# DevBoard.net
KiCad netlist of a schematic drawn in Altium Designer
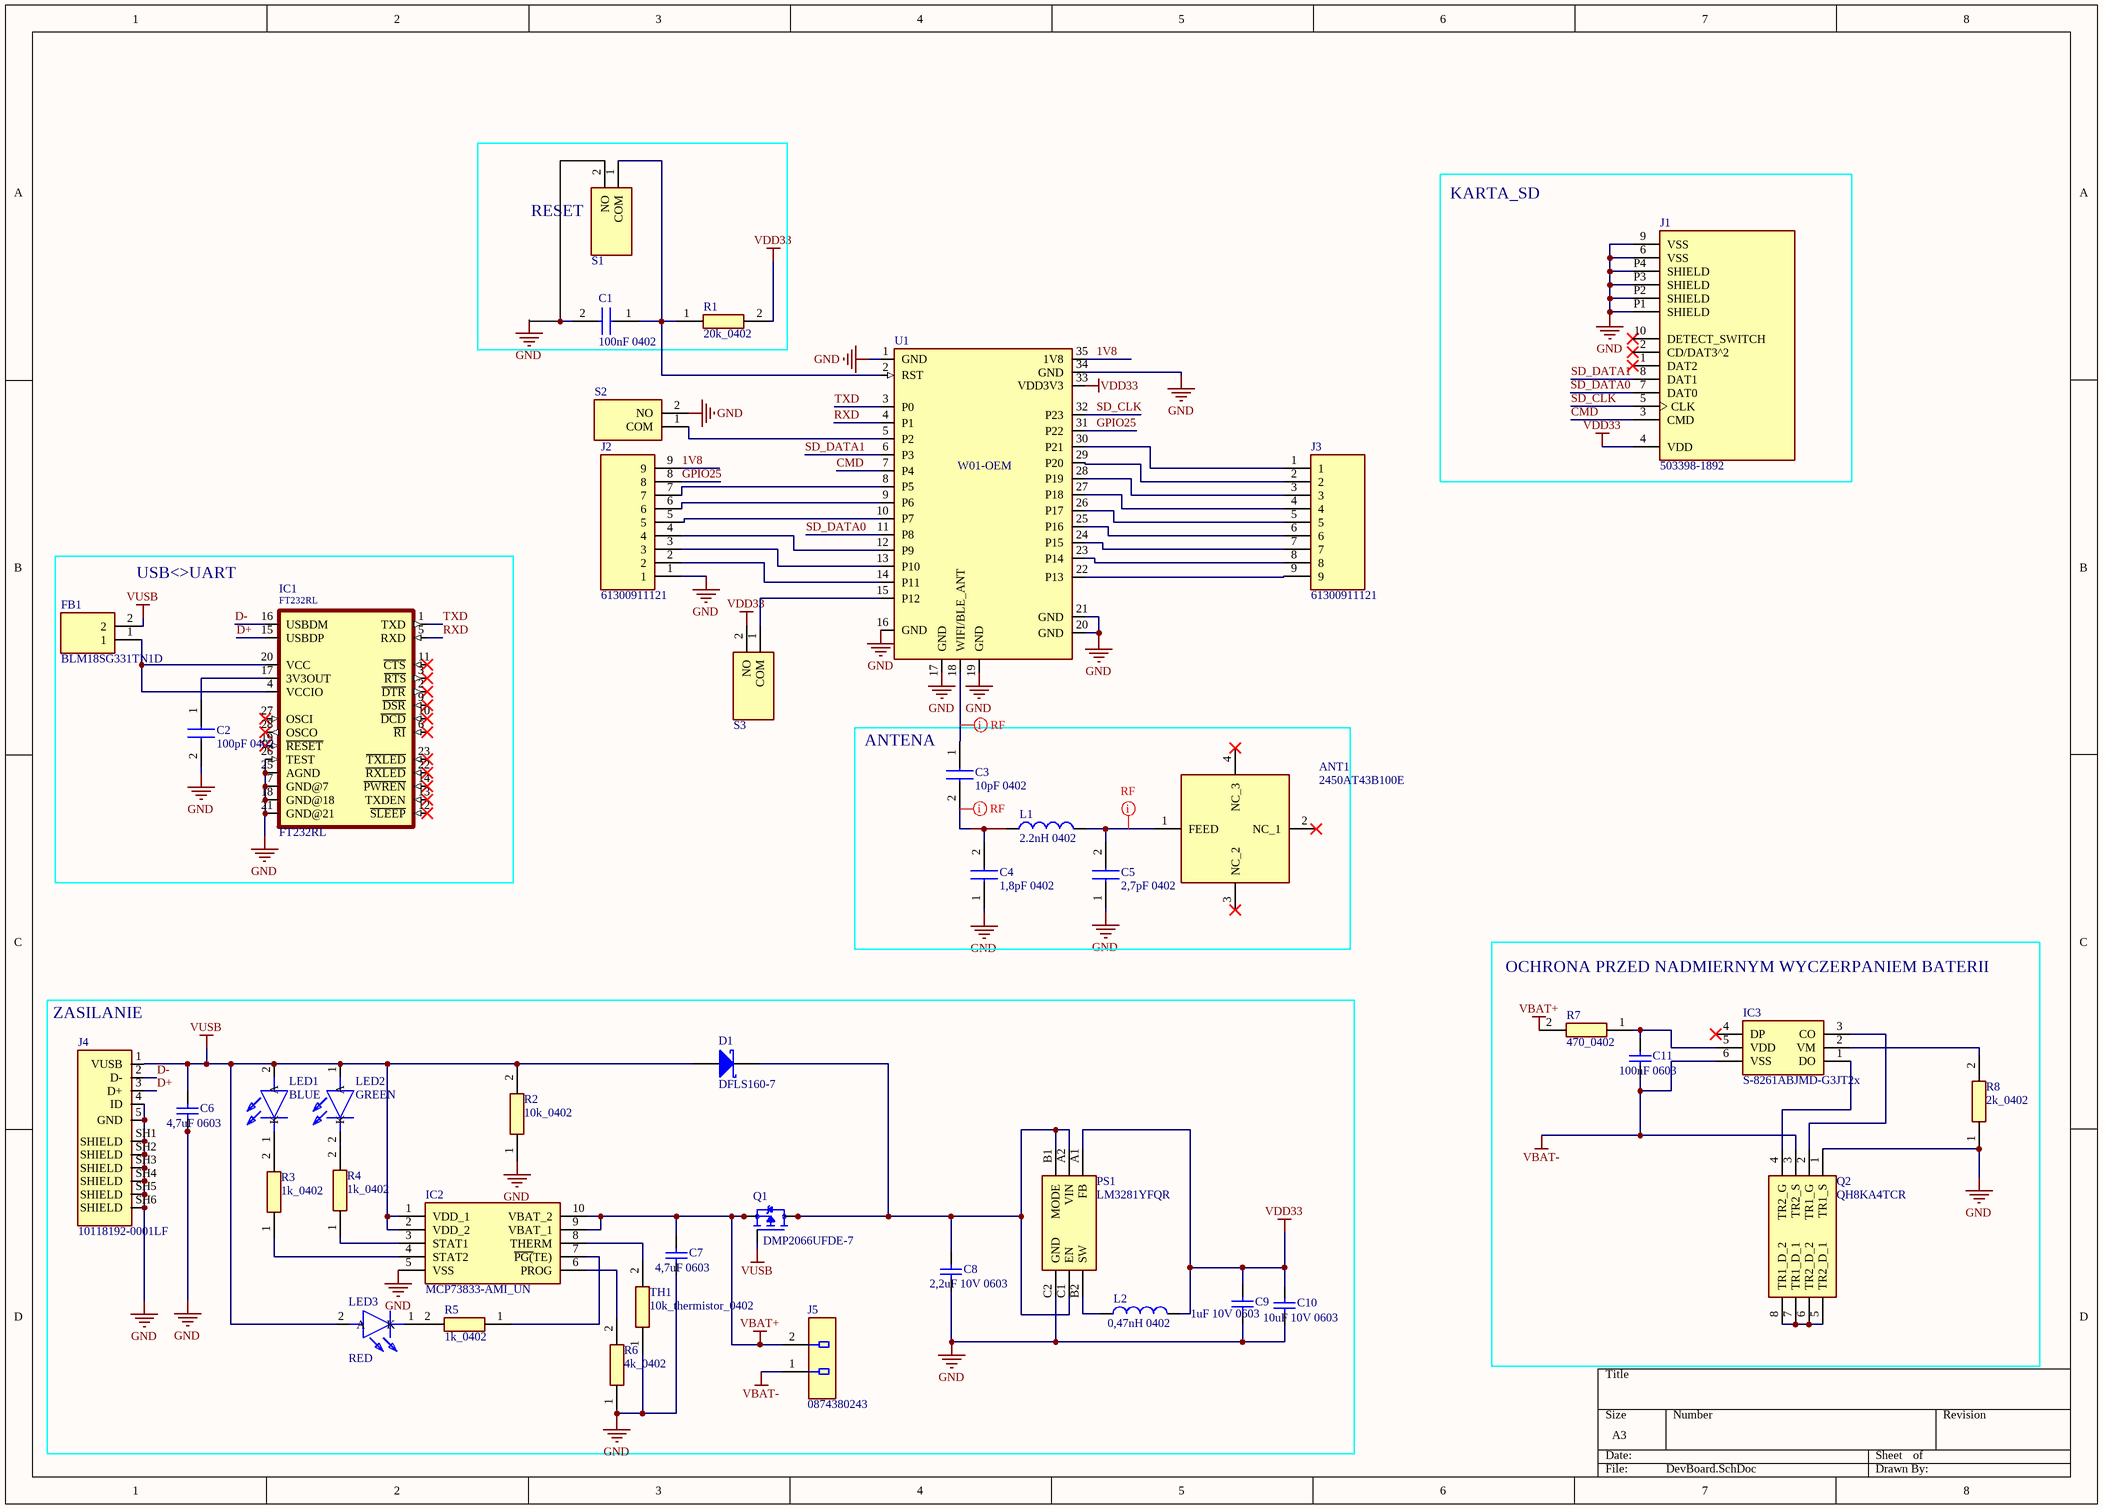
[diagram p0: DevBoard.SchDoc]

(export (version "E")
  (design (tool "Eeschema 10.0.6"))
  (components
    (comp (ref "ANT1")
      (value "2450AT43B100E")
      (footprint "SamacSys:2450AT43B100E")
      (description "Antenna")
      (fields (field (name "MOUSER PART NUMBER") "609-2450AT43B100E"))
      (libsource (lib "*") (part "2450AT43B100E"))
    )
    (comp (ref "C1")
      (value "100nF 0402")
      (footprint "SamacSys:CAPC1005X56N")
      (description "Capacitor")
      (fields
        (field (name "MANUFACTURER_PART_NUMBER") "04025A1R8BAT2A")
        (field (name "MOUSER PART NUMBER") "581-04025A1R8BAT2A")
      )
      (libsource (lib "*") (part "04025A1R8BAT2A"))
    )
    (comp (ref "C2")
      (value "100pF 0402")
      (footprint "SamacSys:CAPC1005X56N")
      (description "Capacitor")
      (fields
        (field (name "MANUFACTURER_PART_NUMBER") "04025A1R8BAT2A")
        (field (name "MOUSER PART NUMBER") "581-04025A1R8BAT2A")
      )
      (libsource (lib "*") (part "04025A1R8BAT2A"))
    )
    (comp (ref "C3")
      (value "10pF 0402")
      (footprint "SamacSys:CAPC1005X56N")
      (description "Capacitor")
      (fields
        (field (name "MANUFACTURER_PART_NUMBER") "04025A1R8BAT2A")
        (field (name "MOUSER PART NUMBER") "581-04025A1R8BAT2A")
      )
      (libsource (lib "*") (part "04025A1R8BAT2A"))
    )
    (comp (ref "C4")
      (value "1,8pF 0402")
      (footprint "SamacSys:CAPC1005X56N")
      (description "Capacitor")
      (fields
        (field (name "MANUFACTURER_PART_NUMBER") "04025A1R8BAT2A")
        (field (name "MOUSER PART NUMBER") "581-04025A1R8BAT2A")
      )
      (libsource (lib "*") (part "04025A1R8BAT2A"))
    )
    (comp (ref "C5")
      (value "2,7pF 0402")
      (footprint "SamacSys:CAPC1005X56N")
      (description "Capacitor")
      (fields
        (field (name "MANUFACTURER_PART_NUMBER") "04025A1R8BAT2A")
        (field (name "MOUSER PART NUMBER") "581-04025A1R8BAT2A")
      )
      (libsource (lib "*") (part "04025A1R8BAT2A"))
    )
    (comp (ref "C6")
      (value "4,7uF 0603")
      (footprint "CAPC0603(1608)100_L")
      (description "CAP 1uF 10V ±20% 0603 (1608 Metric) Thickness 1mm SMD")
      (fields (field (name "TOLERANCE") "Â±20%"))
      (libsource (lib "Altium Content Vault") (part "CMP-1035-02734-1"))
    )
    (comp (ref "C7")
      (value "4,7uF 0603")
      (footprint "CAPC0603(1608)100_L")
      (description "CAP 1uF 10V ±20% 0603 (1608 Metric) Thickness 1mm SMD")
      (fields (field (name "TOLERANCE") "Â±20%"))
      (libsource (lib "Altium Content Vault") (part "CMP-1035-02734-1"))
    )
    (comp (ref "C8")
      (value "2,2uF 10V 0603")
      (footprint "CAPC0603(1608)100_L")
      (description "CAP 1uF 10V ±20% 0603 (1608 Metric) Thickness 1mm SMD")
      (fields (field (name "TOLERANCE") "Â±20%"))
      (libsource (lib "Altium Content Vault") (part "CMP-1035-02734-1"))
    )
    (comp (ref "C9")
      (value "1uF 10V 0603")
      (footprint "CAPC0603(1608)100_L")
      (description "CAP 1uF 10V ±20% 0603 (1608 Metric) Thickness 1mm SMD")
      (fields (field (name "TOLERANCE") "Â±20%"))
      (libsource (lib "Altium Content Vault") (part "CAP"))
    )
    (comp (ref "C10")
      (value "10uF 10V 0603")
      (footprint "CAPC0603(1608)100_L")
      (description "CAP 1uF 10V ±20% 0603 (1608 Metric) Thickness 1mm SMD")
      (fields (field (name "TOLERANCE") "Â±20%"))
      (libsource (lib "Altium Content Vault") (part "CMP-1035-02734-1"))
    )
    (comp (ref "C11")
      (value "100nF 0603")
      (footprint "CAPC0603(1608)100_L")
      (description "CAP 1uF 10V ±20% 0603 (1608 Metric) Thickness 1mm SMD")
      (fields (field (name "TOLERANCE") "Â±20%"))
      (libsource (lib "Altium Content Vault") (part "CMP-1035-02734-1"))
    )
    (comp (ref "D1")
      (value "DFLS160-7")
      (footprint "DIOD-POWERDI123-2_V")
      (description "Schottky Barrier Rectifier, 60 V, 1 A, -65 to 150 degC, 2-Pin SMD, RoHS, Tape and Reel")
      (fields (field (name "MANUFACTURER") "Diodes Inc"))
      (libsource (lib "Altium Content Vault") (part "CMP-2000-07449-1"))
    )
    (comp (ref "FB1")
      (value "BLM18SG331TN1D")
      (footprint "SamacSys:BLM18SG121TN1J")
      (description "Ferrite Bead")
      (fields (field (name "MOUSER PART NUMBER") "81-BLM18SG331TN1D"))
      (libsource (lib "*") (part "BLM18SG331TN1D"))
    )
    (comp (ref "IC1")
      (value "FT232RL")
      (footprint "SSOP28-LD")
      (description "USB ë¸Œë¦¬ì§€, USB-UART USB 2.0 UART ì¸í„°íŽ˜ì´ìŠ¤ 28-SSOP")
      (fields (field (name "MF") "FTDI, Future"))
      (libsource (lib "FT232RL") (part "FT232RL"))
    )
    (comp (ref "IC2")
      (value "MCP73833-AMI_UN")
      (footprint "SamacSys:SOP50P490X110-10N")
      (description "Integrated Circuit")
      (fields
        (field (name "MANUFACTURER_PART_NUMBER") "MCP73833-AMI/UN")
        (field (name "MOUSER PART NUMBER") "579-MCP73833-AMI/UN")
      )
      (libsource (lib "*") (part "MCP73833-AMI_UN"))
    )
    (comp (ref "IC3")
      (value "S-8261ABJMD-G3JT2x")
      (footprint "SamacSys:SOT95P275X135-6N")
      (description "Integrated Circuit")
      (fields (field (name "MOUSER PART NUMBER") "628-S8261ACMMDG4MT2G"))
      (libsource (lib "*") (part "S-8261ACMMD-G4MT2U"))
    )
    (comp (ref "J1")
      (value "503398-1892")
      (footprint "MOLEX_503398-1892")
      (description "9 _8 + 1_ Position Card Connector microSDâ„¢ Surface Mount, Right Angle Gold")
      (fields (field (name "MP") "5033981892") (field (name "DIGI-KEY_PART_NUMBER") "WM11190CT-ND"))
      (libsource (lib "503398-1892") (part "503398-1892"))
    )
    (comp (ref "J2")
      (value "61300911121")
      (footprint "SamacSys:HDRV9W95P0X254_1X9_2286X254X874P")
      (description "Connector")
      (fields (field (name "MOUSER PART NUMBER") "710-61300911121"))
      (libsource (lib "*") (part "61300911121"))
    )
    (comp (ref "J3")
      (value "61300911121")
      (footprint "SamacSys:HDRV9W95P0X254_1X9_2286X254X874P")
      (description "Connector")
      (fields (field (name "MOUSER PART NUMBER") "710-61300911121"))
      (libsource (lib "") (part "61300911121_1"))
    )
    (comp (ref "J4")
      (value "10118192-0001LF")
      (footprint "SamacSys:101181920001LF")
      (description "USB - micro B USB 2.0 Receptacle Connector 5 Position Surface Mount, Right Angle")
      (fields (field (name "MF") "Amphenol ICC"))
      (libsource (lib "10118192-0001LF") (part "10118192-0001LF"))
    )
    (comp (ref "J5")
      (value "Conn_Molex_0874380243_eec")
      (footprint "Molex_0874380243_0")
      (description "CONN HEADER 2POS 1.5MM R/A SMD")
      (fields
        (field (name "PART NUMBER") "0874380243")
        (field (name "MANUFACTURER") "Molex")
        (field (name "MOUSER PART NUMBER") "538-87438-0243")
      )
      (libsource (lib "Conn_Molex_0874380243_eec") (part "Conn_Molex_0874380243_eec"))
    )
    (comp (ref "L1")
      (value "2.2nH 0402")
      (footprint "INDC1006X60X20LL10T10")
      (description "Chip Inductor, 10 nH, +/- 5%, 500 mA, -55 to 125 degC, 0402 (1005 Metric), RoHS, Tape and Reel")
      (fields (field (name "MANUFACTURER") "Murata"))
      (libsource (lib "Altium Content Vault") (part "IND-2"))
    )
    (comp (ref "L2")
      (value "0,47nH 0402")
      (footprint "INDC1006X60X20LL10T10")
      (description "Chip Inductor, 10 nH, +/- 5%, 500 mA, -55 to 125 degC, 0402 (1005 Metric), RoHS, Tape and Reel")
      (fields (field (name "MANUFACTURER") "Murata"))
      (libsource (lib "Altium Content Vault") (part "IND-2"))
    )
    (comp (ref "LED1")
      (value "BLUE")
      (footprint "SamacSys:KBDELPS212QHRI24Z55510S")
      (description "LED_BLUE")
      (fields
        (field (name "MANUFACTURER_PART_NUMBER") "KB DELPS2.12-QHRI-24-Z555-10-S")
        (field (name "MOUSER PART NUMBER") "720-KBDELPS212A6350")
      )
      (libsource (lib "*") (part "KB_DELPS2.12-QHRI-24-Z555-10-S"))
    )
    (comp (ref "LED2")
      (value "GREEN")
      (footprint "SamacSys:KGDELLS122JGKH24")
      (description "LED_GREEN")
      (fields
        (field (name "MANUFACTURER_PART_NUMBER") "KG DELLS1.22-JGKH-24")
        (field (name "MOUSER PART NUMBER") "720-KGDELLS122A4849")
      )
      (libsource (lib "*") (part "KG_DELLS1.22-JGKH-24"))
    )
    (comp (ref "LED3")
      (value "RED")
      (footprint "SamacSys:KRDELPS122UHVI26H3Q4")
      (description "LED_RED")
      (fields
        (field (name "MANUFACTURER_PART_NUMBER") "KR DELPS1.22-UHVI-26-H3Q4")
        (field (name "MOUSER PART NUMBER") "720-KRDELPS122A5163")
      )
      (libsource (lib "*") (part "KR_DELPS1.22-UHVI-26-H3Q4"))
    )
    (comp (ref "PS1")
      (value "LM3281YFQR")
      (footprint "SamacSys:BGA6C40P2X3_116X144X68")
      (description "Power Supply")
      (fields (field (name "MOUSER PART NUMBER") "595-LM3281YFQR"))
      (libsource (lib "*") (part "LM3281YFQR"))
    )
    (comp (ref "Q1")
      (value "DMP2066UFDE-7")
      (footprint "MOSFET_DMP2066UFDE-7")
      (description "P-Channel 20V 6.2A (Ta) 660mW (Ta) Surface Mount U-DFN2020-6 (Type E)")
      (fields (field (name "MF") "Diodes Inc."))
      (libsource (lib "DMP2066UFDE-7") (part "DMP2066UFDE-7"))
    )
    (comp (ref "Q2")
      (value "QH8KA4TCR")
      (footprint "SamacSys:SOTFL65P280X85-8N")
      (description "MOSFET (N-Channel)")
      (fields (field (name "MOUSER PART NUMBER") "755-QH8KA4TCR"))
      (libsource (lib "*") (part "QH8KA4TCR"))
    )
    (comp (ref "R1")
      (value "20k_0402")
      (footprint "SamacSys:RESC1005X40N")
      (description "Resistor")
      (fields
        (field (name "MANUFACTURER_PART_NUMBER") "CR0402-FX-2002GLF")
        (field (name "MOUSER PART NUMBER") "652-CR0402FX-2002GLF")
      )
      (libsource (lib "") (part "CR0402-FX-2002GLF_2"))
    )
    (comp (ref "R2")
      (value "10k_0402")
      (footprint "SamacSys:RESC1005X40N")
      (description "Resistor")
      (fields
        (field (name "MANUFACTURER_PART_NUMBER") "CR0402-FX-2002GLF")
        (field (name "MOUSER PART NUMBER") "652-CR0402FX-2002GLF")
      )
      (libsource (lib "") (part "CR0402-FX-2002GLF_1"))
    )
    (comp (ref "R3")
      (value "1k_0402")
      (footprint "SamacSys:RESC1005X40N")
      (description "Resistor")
      (fields
        (field (name "MANUFACTURER_PART_NUMBER") "CR0402-FX-2002GLF")
        (field (name "MOUSER PART NUMBER") "652-CR0402FX-2002GLF")
      )
      (libsource (lib "") (part "CR0402-FX-2002GLF_1"))
    )
    (comp (ref "R4")
      (value "1k_0402")
      (footprint "SamacSys:RESC1005X40N")
      (description "Resistor")
      (fields
        (field (name "MANUFACTURER_PART_NUMBER") "CR0402-FX-2002GLF")
        (field (name "MOUSER PART NUMBER") "652-CR0402FX-2002GLF")
      )
      (libsource (lib "") (part "CR0402-FX-2002GLF_1"))
    )
    (comp (ref "R5")
      (value "1k_0402")
      (footprint "SamacSys:RESC1005X40N")
      (description "Resistor")
      (fields
        (field (name "MANUFACTURER_PART_NUMBER") "CR0402-FX-2002GLF")
        (field (name "MOUSER PART NUMBER") "652-CR0402FX-2002GLF")
      )
      (libsource (lib "*") (part "CR0402-FX-2002GLF"))
    )
    (comp (ref "R6")
      (value "4k_0402")
      (footprint "SamacSys:RESC1005X40N")
      (description "Resistor")
      (fields
        (field (name "MANUFACTURER_PART_NUMBER") "CR0402-FX-2002GLF")
        (field (name "MOUSER PART NUMBER") "652-CR0402FX-2002GLF")
      )
      (libsource (lib "") (part "CR0402-FX-2002GLF_1"))
    )
    (comp (ref "R7")
      (value "470_0402")
      (footprint "SamacSys:RESC1005X40N")
      (description "Resistor")
      (fields
        (field (name "MANUFACTURER_PART_NUMBER") "CR0402-FX-2002GLF")
        (field (name "MOUSER PART NUMBER") "652-CR0402FX-2002GLF")
      )
      (libsource (lib "*") (part "CR0402-FX-2002GLF"))
    )
    (comp (ref "R8")
      (value "2k_0402")
      (footprint "SamacSys:RESC1005X40N")
      (description "Resistor")
      (fields
        (field (name "MANUFACTURER_PART_NUMBER") "CR0402-FX-2002GLF")
        (field (name "MOUSER PART NUMBER") "652-CR0402FX-2002GLF")
      )
      (libsource (lib "") (part "CR0402-FX-2002GLF_1"))
    )
    (comp (ref "S1")
      (value "PTS636_SM43J_SMTR_LFS")
      (footprint "SamacSys:PTS636SM43JSMTRLFS")
      (description "Switch")
      (fields
        (field (name "MANUFACTURER_PART_NUMBER") "PTS636 SM43J SMTR LFS")
        (field (name "MOUSER PART NUMBER") "611-PTS636SM43JSMTRL")
      )
      (libsource (lib "*") (part "PTS636_SM43J_SMTR_LFS"))
    )
    (comp (ref "S2")
      (value "PTS636_SM43J_SMTR_LFS")
      (footprint "SamacSys:PTS636SM43JSMTRLFS")
      (description "Switch")
      (fields
        (field (name "MANUFACTURER_PART_NUMBER") "PTS636 SM43J SMTR LFS")
        (field (name "MOUSER PART NUMBER") "611-PTS636SM43JSMTRL")
      )
      (libsource (lib "") (part "PTS636_SM43J_SMTR_LFS_1"))
    )
    (comp (ref "S3")
      (value "PTS636_SM43J_SMTR_LFS")
      (footprint "SamacSys:PTS636SM43JSMTRLFS")
      (description "Switch")
      (fields
        (field (name "MANUFACTURER_PART_NUMBER") "PTS636 SM43J SMTR LFS")
        (field (name "MOUSER PART NUMBER") "611-PTS636SM43JSMTRL")
      )
      (libsource (lib "*") (part "PTS636_SM43J_SMTR_LFS"))
    )
    (comp (ref "TH1")
      (value "10k_thermistor_0402")
      (footprint "SamacSys:RESC1005X40N")
      (description "NCU15XH103D60RC")
      (fields
        (field (name "MANUFACTURER_PART_NUMBER") "CR0402-FX-2002GLF")
        (field (name "MOUSER PART NUMBER") "652-CR0402FX-2002GLF")
      )
      (libsource (lib "") (part "CR0402-FX-2002GLF_1"))
    )
    (comp (ref "U1")
      (value "W01-OEM")
      (footprint "SnapEDApcb:PYCOM_W01-OEM")
      (fields (field (name "MF") "Pycom"))
      (libsource (lib "SnapEDAsch") (part "W01-OEM"))
    )
  )
  (nets
    (net (code "1") (name "/1V8") (class "Default")
      (node (ref "J2") (pin "9") (pinfunction "9_9") (pintype "passive"))
      (node (ref "U1") (pin "35") (pinfunction "1V8_35") (pintype "power_in"))
    )
    (net (code "2") (name "/CMD") (class "Default")
      (node (ref "J1") (pin "3") (pinfunction "CMD_3") (pintype "passive"))
      (node (ref "U1") (pin "7") (pinfunction "P4_7") (pintype "bidirectional"))
    )
    (net (code "3") (name "/D+") (class "Default")
      (node (ref "IC1") (pin "15") (pinfunction "USBDP_15") (pintype "bidirectional"))
      (node (ref "J4") (pin "3") (pinfunction "D+_3") (pintype "passive"))
    )
    (net (code "4") (name "/D-") (class "Default")
      (node (ref "IC1") (pin "16") (pinfunction "USBDM_16") (pintype "bidirectional"))
      (node (ref "J4") (pin "2") (pinfunction "D-_2") (pintype "passive"))
    )
    (net (code "5") (name "/GPIO25") (class "Default")
      (node (ref "J2") (pin "8") (pinfunction "8_8") (pintype "passive"))
      (node (ref "U1") (pin "31") (pinfunction "P22_31") (pintype "bidirectional"))
    )
    (net (code "6") (name "/RXD") (class "Default")
      (node (ref "IC1") (pin "5") (pinfunction "RXD_5") (pintype "input"))
      (node (ref "U1") (pin "4") (pinfunction "P1_4") (pintype "bidirectional"))
    )
    (net (code "7") (name "/SD_CLK") (class "Default")
      (node (ref "J1") (pin "5") (pinfunction "CLK_5") (pintype "passive"))
      (node (ref "U1") (pin "32") (pinfunction "P23_32") (pintype "bidirectional"))
    )
    (net (code "8") (name "/SD_DATA0") (class "Default")
      (node (ref "J1") (pin "7") (pinfunction "DAT0_7") (pintype "passive"))
      (node (ref "U1") (pin "11") (pinfunction "P8_11") (pintype "bidirectional"))
    )
    (net (code "9") (name "/SD_DATA1") (class "Default")
      (node (ref "J1") (pin "8") (pinfunction "DAT1_8") (pintype "passive"))
      (node (ref "U1") (pin "6") (pinfunction "P3_6") (pintype "bidirectional"))
    )
    (net (code "10") (name "/TXD") (class "Default")
      (node (ref "IC1") (pin "1") (pinfunction "TXD_1") (pintype "output"))
      (node (ref "U1") (pin "3") (pinfunction "P0_3") (pintype "bidirectional"))
    )
    (net (code "11") (name "GND") (class "Default")
      (node (ref "C1") (pin "2") (pinfunction "2_2") (pintype "passive"))
      (node (ref "C10") (pin "1") (pinfunction "1_1") (pintype "passive"))
      (node (ref "C2") (pin "2") (pinfunction "2_2") (pintype "passive"))
      (node (ref "C4") (pin "1") (pinfunction "1_1") (pintype "passive"))
      (node (ref "C5") (pin "1") (pinfunction "1_1") (pintype "passive"))
      (node (ref "C6") (pin "1") (pinfunction "1_1") (pintype "passive"))
      (node (ref "C7") (pin "1") (pinfunction "1_1") (pintype "passive"))
      (node (ref "C8") (pin "1") (pinfunction "1_1") (pintype "passive"))
      (node (ref "C9") (pin "1") (pinfunction "1_1") (pintype "passive"))
      (node (ref "IC1") (pin "18") (pinfunction "GND@18_18") (pintype "power_in"))
      (node (ref "IC1") (pin "21") (pinfunction "GND@21_21") (pintype "power_in"))
      (node (ref "IC1") (pin "25") (pinfunction "AGND_25") (pintype "power_in"))
      (node (ref "IC1") (pin "26") (pinfunction "TEST_26") (pintype "input"))
      (node (ref "IC1") (pin "7") (pinfunction "GND@7_7") (pintype "power_in"))
      (node (ref "IC2") (pin "5") (pinfunction "VSS_5") (pintype "passive"))
      (node (ref "J1") (pin "6") (pinfunction "VSS_6") (pintype "power_in"))
      (node (ref "J1") (pin "9") (pinfunction "VSS_9") (pintype "power_in"))
      (node (ref "J1") (pin "P1") (pinfunction "SHIELD_P1") (pintype "passive"))
      (node (ref "J1") (pin "P2") (pinfunction "SHIELD_P2") (pintype "passive"))
      (node (ref "J1") (pin "P3") (pinfunction "SHIELD_P3") (pintype "passive"))
      (node (ref "J1") (pin "P4") (pinfunction "SHIELD_P4") (pintype "passive"))
      (node (ref "J2") (pin "1") (pinfunction "1_1") (pintype "passive"))
      (node (ref "J4") (pin "4") (pinfunction "ID_4") (pintype "passive"))
      (node (ref "J4") (pin "5") (pinfunction "GND_5") (pintype "passive"))
      (node (ref "J4") (pin "SH1") (pinfunction "SHIELD_SH1") (pintype "passive"))
      (node (ref "J4") (pin "SH2") (pinfunction "SHIELD_SH2") (pintype "passive"))
      (node (ref "J4") (pin "SH3") (pinfunction "SHIELD_SH3") (pintype "passive"))
      (node (ref "J4") (pin "SH4") (pinfunction "SHIELD_SH4") (pintype "passive"))
      (node (ref "J4") (pin "SH5") (pinfunction "SHIELD_SH5") (pintype "passive"))
      (node (ref "J4") (pin "SH6") (pinfunction "SHIELD_SH6") (pintype "passive"))
      (node (ref "PS1") (pin "C2") (pinfunction "GND_C2") (pintype "passive"))
      (node (ref "Q2") (pin "1") (pinfunction "TR1_S_1") (pintype "passive"))
      (node (ref "R2") (pin "1") (pinfunction "1_1") (pintype "passive"))
      (node (ref "R6") (pin "1") (pinfunction "1_1") (pintype "passive"))
      (node (ref "R8") (pin "1") (pinfunction "1_1") (pintype "passive"))
      (node (ref "S1") (pin "2") (pinfunction "NO_2") (pintype "passive"))
      (node (ref "S2") (pin "2") (pinfunction "NO_2") (pintype "passive"))
      (node (ref "TH1") (pin "1") (pinfunction "1_1") (pintype "passive"))
      (node (ref "U1") (pin "1") (pinfunction "GND_1") (pintype "power_in"))
      (node (ref "U1") (pin "16") (pinfunction "GND_16") (pintype "power_in"))
      (node (ref "U1") (pin "17") (pinfunction "GND_17") (pintype "power_in"))
      (node (ref "U1") (pin "19") (pinfunction "GND_19") (pintype "power_in"))
      (node (ref "U1") (pin "20") (pinfunction "GND_20") (pintype "power_in"))
      (node (ref "U1") (pin "21") (pinfunction "GND_21") (pintype "power_in"))
      (node (ref "U1") (pin "34") (pinfunction "GND_34") (pintype "power_in"))
    )
    (net (code "12") (name "Net-(ANT1-FEED)") (class "Default")
      (node (ref "ANT1") (pin "1") (pinfunction "FEED_1") (pintype "passive"))
      (node (ref "C5") (pin "2") (pinfunction "2_2") (pintype "passive"))
      (node (ref "L1") (pin "2") (pinfunction "2_2") (pintype "passive"))
    )
    (net (code "13") (name "Net-(C3-Pad2)") (class "Default")
      (node (ref "C3") (pin "2") (pinfunction "2_2") (pintype "passive"))
      (node (ref "C4") (pin "2") (pinfunction "2_2") (pintype "passive"))
      (node (ref "L1") (pin "1") (pinfunction "1_1") (pintype "passive"))
    )
    (net (code "14") (name "Net-(D1-K)") (class "Default")
      (node (ref "C8") (pin "2") (pinfunction "2_2") (pintype "passive"))
      (node (ref "D1") (pin "2") (pinfunction "K_2") (pintype "passive"))
      (node (ref "PS1") (pin "A2") (pinfunction "VIN_A2") (pintype "passive"))
      (node (ref "PS1") (pin "B1") (pinfunction "MODE_B1") (pintype "passive"))
      (node (ref "PS1") (pin "C1") (pinfunction "EN_C1") (pintype "passive"))
      (node (ref "Q1") (pin "1") (pinfunction "D_1") (pintype "passive"))
      (node (ref "Q1") (pin "2") (pinfunction "D_2") (pintype "passive"))
      (node (ref "Q1") (pin "5") (pinfunction "D_5") (pintype "passive"))
      (node (ref "Q1") (pin "6") (pinfunction "D_6") (pintype "passive"))
    )
    (net (code "15") (name "Net-(IC1-3V3OUT)") (class "Default")
      (node (ref "C2") (pin "1") (pinfunction "1_1") (pintype "passive"))
      (node (ref "IC1") (pin "17") (pinfunction "3V3OUT_17") (pintype "power_in"))
    )
    (net (code "16") (name "Net-(IC1-VCC)") (class "Default")
      (node (ref "FB1") (pin "1") (pinfunction "1_1") (pintype "passive"))
      (node (ref "IC1") (pin "20") (pinfunction "VCC_20") (pintype "power_in"))
      (node (ref "IC1") (pin "4") (pinfunction "VCCIO_4") (pintype "power_in"))
    )
    (net (code "17") (name "Net-(IC2-PROG)") (class "Default")
      (node (ref "IC2") (pin "6") (pinfunction "PROG_6") (pintype "passive"))
      (node (ref "R6") (pin "2") (pinfunction "2_2") (pintype "passive"))
    )
    (net (code "18") (name "Net-(IC2-STAT1)") (class "Default")
      (node (ref "IC2") (pin "3") (pinfunction "STAT1_3") (pintype "passive"))
      (node (ref "R4") (pin "1") (pinfunction "1_1") (pintype "passive"))
    )
    (net (code "19") (name "Net-(IC2-STAT2)") (class "Default")
      (node (ref "IC2") (pin "4") (pinfunction "STAT2_4") (pintype "passive"))
      (node (ref "R3") (pin "1") (pinfunction "1_1") (pintype "passive"))
    )
    (net (code "20") (name "Net-(IC2-THERM)") (class "Default")
      (node (ref "IC2") (pin "8") (pinfunction "THERM_8") (pintype "passive"))
      (node (ref "TH1") (pin "2") (pinfunction "2_2") (pintype "passive"))
    )
    (net (code "21") (name "Net-(IC2-~{PG(}TE))") (class "Default")
      (node (ref "IC2") (pin "7") (pinfunction "~{PG(}TE)_7") (pintype "passive"))
      (node (ref "R5") (pin "1") (pinfunction "1_1") (pintype "passive"))
    )
    (net (code "22") (name "Net-(IC3-CO)") (class "Default")
      (node (ref "IC3") (pin "3") (pinfunction "CO_3") (pintype "passive"))
      (node (ref "Q2") (pin "2") (pinfunction "TR1_G_2") (pintype "passive"))
    )
    (net (code "23") (name "Net-(IC3-DO)") (class "Default")
      (node (ref "IC3") (pin "1") (pinfunction "DO_1") (pintype "passive"))
      (node (ref "Q2") (pin "4") (pinfunction "TR2_G_4") (pintype "passive"))
    )
    (net (code "24") (name "Net-(IC3-VDD)") (class "Default")
      (node (ref "C11") (pin "2") (pinfunction "2_2") (pintype "passive"))
      (node (ref "IC3") (pin "5") (pinfunction "VDD_5") (pintype "passive"))
      (node (ref "R7") (pin "1") (pinfunction "1_1") (pintype "passive"))
    )
    (net (code "25") (name "Net-(IC3-VM)") (class "Default")
      (node (ref "IC3") (pin "2") (pinfunction "VM_2") (pintype "passive"))
      (node (ref "R8") (pin "2") (pinfunction "2_2") (pintype "passive"))
    )
    (net (code "26") (name "Net-(LED1-K)") (class "Default")
      (node (ref "LED1") (pin "1") (pinfunction "K_1") (pintype "passive"))
      (node (ref "R3") (pin "2") (pinfunction "2_2") (pintype "passive"))
    )
    (net (code "27") (name "Net-(LED2-K)") (class "Default")
      (node (ref "LED2") (pin "2") (pinfunction "K_2") (pintype "passive"))
      (node (ref "R4") (pin "2") (pinfunction "2_2") (pintype "passive"))
    )
    (net (code "28") (name "Net-(LED3-K)") (class "Default")
      (node (ref "LED3") (pin "1") (pinfunction "K_1") (pintype "passive"))
      (node (ref "R5") (pin "2") (pinfunction "2_2") (pintype "passive"))
    )
    (net (code "29") (name "Net-(PS1-SW)") (class "Default")
      (node (ref "L2") (pin "1") (pinfunction "1_1") (pintype "passive"))
      (node (ref "PS1") (pin "B2") (pinfunction "SW_B2") (pintype "passive"))
    )
    (net (code "30") (name "Net-(Q2-TR1_D_1)") (class "Default")
      (node (ref "Q2") (pin "5") (pinfunction "TR2_D_1_5") (pintype "passive"))
      (node (ref "Q2") (pin "6") (pinfunction "TR2_D_2_6") (pintype "passive"))
      (node (ref "Q2") (pin "7") (pinfunction "TR1_D_1_7") (pintype "passive"))
      (node (ref "Q2") (pin "8") (pinfunction "TR1_D_2_8") (pintype "passive"))
    )
    (net (code "31") (name "Net-(S1-COM)") (class "Default")
      (node (ref "C1") (pin "1") (pinfunction "1_1") (pintype "passive"))
      (node (ref "R1") (pin "1") (pinfunction "1_1") (pintype "passive"))
      (node (ref "S1") (pin "1") (pinfunction "COM_1") (pintype "passive"))
      (node (ref "U1") (pin "2") (pinfunction "RST_2") (pintype "input"))
    )
    (net (code "32") (name "Net-(S2-COM)") (class "Default")
      (node (ref "S2") (pin "1") (pinfunction "COM_1") (pintype "passive"))
      (node (ref "U1") (pin "5") (pinfunction "P2_5") (pintype "bidirectional"))
    )
    (net (code "33") (name "Net-(S3-COM)") (class "Default")
      (node (ref "S3") (pin "1") (pinfunction "COM_1") (pintype "passive"))
      (node (ref "U1") (pin "15") (pinfunction "P12_15") (pintype "bidirectional"))
    )
    (net (code "34") (name "Net-(U1-P5)") (class "Default")
      (node (ref "J2") (pin "7") (pinfunction "7_7") (pintype "passive"))
      (node (ref "U1") (pin "8") (pinfunction "P5_8") (pintype "bidirectional"))
    )
    (net (code "35") (name "Net-(U1-P6)") (class "Default")
      (node (ref "J2") (pin "6") (pinfunction "6_6") (pintype "passive"))
      (node (ref "U1") (pin "9") (pinfunction "P6_9") (pintype "bidirectional"))
    )
    (net (code "36") (name "Net-(U1-P7)") (class "Default")
      (node (ref "J2") (pin "5") (pinfunction "5_5") (pintype "passive"))
      (node (ref "U1") (pin "10") (pinfunction "P7_10") (pintype "bidirectional"))
    )
    (net (code "37") (name "Net-(U1-P9)") (class "Default")
      (node (ref "J2") (pin "4") (pinfunction "4_4") (pintype "passive"))
      (node (ref "U1") (pin "12") (pinfunction "P9_12") (pintype "bidirectional"))
    )
    (net (code "38") (name "Net-(U1-P10)") (class "Default")
      (node (ref "J2") (pin "3") (pinfunction "3_3") (pintype "passive"))
      (node (ref "U1") (pin "13") (pinfunction "P10_13") (pintype "bidirectional"))
    )
    (net (code "39") (name "Net-(U1-P11)") (class "Default")
      (node (ref "J2") (pin "2") (pinfunction "2_2") (pintype "passive"))
      (node (ref "U1") (pin "14") (pinfunction "P11_14") (pintype "bidirectional"))
    )
    (net (code "40") (name "Net-(U1-P13)") (class "Default")
      (node (ref "J3") (pin "9") (pinfunction "9_9") (pintype "passive"))
      (node (ref "U1") (pin "22") (pinfunction "P13_22") (pintype "bidirectional"))
    )
    (net (code "41") (name "Net-(U1-P14)") (class "Default")
      (node (ref "J3") (pin "8") (pinfunction "8_8") (pintype "passive"))
      (node (ref "U1") (pin "23") (pinfunction "P14_23") (pintype "bidirectional"))
    )
    (net (code "42") (name "Net-(U1-P15)") (class "Default")
      (node (ref "J3") (pin "7") (pinfunction "7_7") (pintype "passive"))
      (node (ref "U1") (pin "24") (pinfunction "P15_24") (pintype "bidirectional"))
    )
    (net (code "43") (name "Net-(U1-P16)") (class "Default")
      (node (ref "J3") (pin "6") (pinfunction "6_6") (pintype "passive"))
      (node (ref "U1") (pin "25") (pinfunction "P16_25") (pintype "bidirectional"))
    )
    (net (code "44") (name "Net-(U1-P17)") (class "Default")
      (node (ref "J3") (pin "5") (pinfunction "5_5") (pintype "passive"))
      (node (ref "U1") (pin "26") (pinfunction "P17_26") (pintype "bidirectional"))
    )
    (net (code "45") (name "Net-(U1-P18)") (class "Default")
      (node (ref "J3") (pin "4") (pinfunction "4_4") (pintype "passive"))
      (node (ref "U1") (pin "27") (pinfunction "P18_27") (pintype "bidirectional"))
    )
    (net (code "46") (name "Net-(U1-P19)") (class "Default")
      (node (ref "J3") (pin "3") (pinfunction "3_3") (pintype "passive"))
      (node (ref "U1") (pin "28") (pinfunction "P19_28") (pintype "bidirectional"))
    )
    (net (code "47") (name "Net-(U1-P20)") (class "Default")
      (node (ref "J3") (pin "2") (pinfunction "2_2") (pintype "passive"))
      (node (ref "U1") (pin "29") (pinfunction "P20_29") (pintype "bidirectional"))
    )
    (net (code "48") (name "Net-(U1-P21)") (class "Default")
      (node (ref "J3") (pin "1") (pinfunction "1_1") (pintype "passive"))
      (node (ref "U1") (pin "30") (pinfunction "P21_30") (pintype "bidirectional"))
    )
    (net (code "49") (name "Net-(U1-WIFI{slash}BLE_ANT)") (class "Default")
      (node (ref "C3") (pin "1") (pinfunction "1_1") (pintype "passive"))
      (node (ref "U1") (pin "18") (pinfunction "WIFI/BLE_ANT_18") (pintype "bidirectional"))
    )
    (net (code "50") (name "VBAT+") (class "Default")
      (node (ref "C7") (pin "2") (pinfunction "2_2") (pintype "passive"))
      (node (ref "IC2") (pin "10") (pinfunction "VBAT_2_10") (pintype "passive"))
      (node (ref "IC2") (pin "9") (pinfunction "VBAT_1_9") (pintype "passive"))
      (node (ref "J5") (pin "2") (pinfunction "2_2") (pintype "passive"))
      (node (ref "Q1") (pin "4") (pinfunction "S_4") (pintype "passive"))
      (node (ref "Q1") (pin "7") (pinfunction "S_7") (pintype "passive"))
      (node (ref "R7") (pin "2") (pinfunction "2_2") (pintype "passive"))
    )
    (net (code "51") (name "VBAT-") (class "Default")
      (node (ref "C11") (pin "1") (pinfunction "1_1") (pintype "passive"))
      (node (ref "IC3") (pin "6") (pinfunction "VSS_6") (pintype "passive"))
      (node (ref "J5") (pin "1") (pinfunction "1_1") (pintype "passive"))
      (node (ref "Q2") (pin "3") (pinfunction "TR2_S_3") (pintype "passive"))
    )
    (net (code "52") (name "VDD33") (class "Default")
      (node (ref "C10") (pin "2") (pinfunction "2_2") (pintype "passive"))
      (node (ref "C9") (pin "2") (pinfunction "2_2") (pintype "passive"))
      (node (ref "J1") (pin "4") (pinfunction "VDD_4") (pintype "power_in"))
      (node (ref "L2") (pin "2") (pinfunction "2_2") (pintype "passive"))
      (node (ref "PS1") (pin "A1") (pinfunction "FB_A1") (pintype "passive"))
      (node (ref "R1") (pin "2") (pinfunction "2_2") (pintype "passive"))
      (node (ref "S3") (pin "2") (pinfunction "NO_2") (pintype "passive"))
      (node (ref "U1") (pin "33") (pinfunction "VDD3V3_33") (pintype "power_in"))
    )
    (net (code "53") (name "VUSB") (class "Default")
      (node (ref "C6") (pin "2") (pinfunction "2_2") (pintype "passive"))
      (node (ref "D1") (pin "1") (pinfunction "A_1") (pintype "passive"))
      (node (ref "FB1") (pin "2") (pinfunction "2_2") (pintype "passive"))
      (node (ref "IC2") (pin "1") (pinfunction "VDD_1_1") (pintype "passive"))
      (node (ref "IC2") (pin "2") (pinfunction "VDD_2_2") (pintype "passive"))
      (node (ref "J4") (pin "1") (pinfunction "VUSB_1") (pintype "passive"))
      (node (ref "LED1") (pin "2") (pinfunction "A_2") (pintype "passive"))
      (node (ref "LED2") (pin "1") (pinfunction "A_1") (pintype "passive"))
      (node (ref "LED3") (pin "2") (pinfunction "A_2") (pintype "passive"))
      (node (ref "Q1") (pin "3") (pinfunction "G_3") (pintype "passive"))
      (node (ref "R2") (pin "2") (pinfunction "2_2") (pintype "passive"))
    )
    (net (code "54") (name "unconnected-(ANT1-NC_1-Pad2)") (class "Default")
      (node (ref "ANT1") (pin "2") (pinfunction "NC_1_2") (pintype "passive+no_connect"))
    )
    (net (code "55") (name "unconnected-(ANT1-NC_2-Pad3)") (class "Default")
      (node (ref "ANT1") (pin "3") (pinfunction "NC_2_3") (pintype "passive+no_connect"))
    )
    (net (code "56") (name "unconnected-(ANT1-NC_3-Pad4)") (class "Default")
      (node (ref "ANT1") (pin "4") (pinfunction "NC_3_4") (pintype "passive+no_connect"))
    )
    (net (code "57") (name "unconnected-(IC1-OSCI-Pad27)") (class "Default")
      (node (ref "IC1") (pin "27") (pinfunction "OSCI_27") (pintype "input+no_connect"))
    )
    (net (code "58") (name "unconnected-(IC1-OSCO-Pad28)") (class "Default")
      (node (ref "IC1") (pin "28") (pinfunction "OSCO_28") (pintype "output+no_connect"))
    )
    (net (code "59") (name "unconnected-(IC1-TXDEN-Pad13)") (class "Default")
      (node (ref "IC1") (pin "13") (pinfunction "TXDEN_13") (pintype "input+no_connect"))
    )
    (net (code "60") (name "unconnected-(IC1-~{CTS}-Pad11)") (class "Default")
      (node (ref "IC1") (pin "11") (pinfunction "~{CTS}_11") (pintype "input+no_connect"))
    )
    (net (code "61") (name "unconnected-(IC1-~{DCD}-Pad10)") (class "Default")
      (node (ref "IC1") (pin "10") (pinfunction "~{DCD}_10") (pintype "input+no_connect"))
    )
    (net (code "62") (name "unconnected-(IC1-~{DSR}-Pad9)") (class "Default")
      (node (ref "IC1") (pin "9") (pinfunction "~{DSR}_9") (pintype "input+no_connect"))
    )
    (net (code "63") (name "unconnected-(IC1-~{DTR}-Pad2)") (class "Default")
      (node (ref "IC1") (pin "2") (pinfunction "~{DTR}_2") (pintype "output+no_connect"))
    )
    (net (code "64") (name "unconnected-(IC1-~{PWREN}-Pad14)") (class "Default")
      (node (ref "IC1") (pin "14") (pinfunction "~{PWREN}_14") (pintype "input+no_connect"))
    )
    (net (code "65") (name "unconnected-(IC1-~{RESET}-Pad19)") (class "Default")
      (node (ref "IC1") (pin "19") (pinfunction "~{RESET}_19") (pintype "input+no_connect"))
    )
    (net (code "66") (name "unconnected-(IC1-~{RI}-Pad6)") (class "Default")
      (node (ref "IC1") (pin "6") (pinfunction "~{RI}_6") (pintype "input+no_connect"))
    )
    (net (code "67") (name "unconnected-(IC1-~{RTS}-Pad3)") (class "Default")
      (node (ref "IC1") (pin "3") (pinfunction "~{RTS}_3") (pintype "output+no_connect"))
    )
    (net (code "68") (name "unconnected-(IC1-~{RXLED}-Pad22)") (class "Default")
      (node (ref "IC1") (pin "22") (pinfunction "~{RXLED}_22") (pintype "input+no_connect"))
    )
    (net (code "69") (name "unconnected-(IC1-~{SLEEP}-Pad12)") (class "Default")
      (node (ref "IC1") (pin "12") (pinfunction "~{SLEEP}_12") (pintype "input+no_connect"))
    )
    (net (code "70") (name "unconnected-(IC1-~{TXLED}-Pad23)") (class "Default")
      (node (ref "IC1") (pin "23") (pinfunction "~{TXLED}_23") (pintype "input+no_connect"))
    )
    (net (code "71") (name "unconnected-(IC3-DP-Pad4)") (class "Default")
      (node (ref "IC3") (pin "4") (pinfunction "DP_4") (pintype "passive+no_connect"))
    )
    (net (code "72") (name "unconnected-(J1-CD{slash}DAT3^2-Pad2)") (class "Default")
      (node (ref "J1") (pin "2") (pinfunction "CD/DAT3^2_2") (pintype "passive+no_connect"))
    )
    (net (code "73") (name "unconnected-(J1-DAT2-Pad1)") (class "Default")
      (node (ref "J1") (pin "1") (pinfunction "DAT2_1") (pintype "passive+no_connect"))
    )
    (net (code "74") (name "unconnected-(J1-DETECT_SWITCH-Pad10)") (class "Default")
      (node (ref "J1") (pin "10") (pinfunction "DETECT_SWITCH_10") (pintype "passive+no_connect"))
    )
  )
)
